# Transducer.net
KiCad netlist of a schematic drawn in Altium Designer
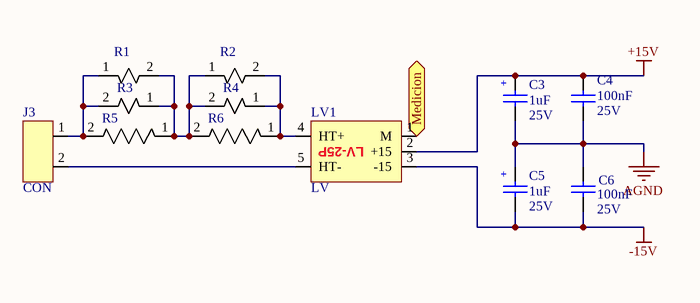
[diagram p0: Transducer.SchDoc]

(export (version "E")
  (design (tool "Eeschema 10.0.6"))
  (components
    (comp (ref "C3")
      (value "1uF")
      (footprint "CAP_1206 Tantalio")
      (description "Capacitor Tantalio")
      (fields (field (name "VOLTAGE") "25V"))
      (libsource (lib "Componentes_SOC") (part "Cap Tantalio 1206"))
    )
    (comp (ref "C4")
      (value "100nF")
      (footprint "CAP_0805")
      (description "Capacitor")
      (fields (field (name "VOLTAGE") "25V"))
      (libsource (lib "Componentes_SOC") (part "Cap_0805"))
    )
    (comp (ref "C5")
      (value "1uF")
      (footprint "CAP_1206 Tantalio")
      (description "Capacitor Tantalio")
      (fields (field (name "VOLTAGE") "25V"))
      (libsource (lib "Componentes_SOC") (part "Cap Tantalio 1206"))
    )
    (comp (ref "C6")
      (value "100nF")
      (footprint "CAP_0805")
      (description "Capacitor")
      (fields (field (name "VOLTAGE") "25V"))
      (libsource (lib "Componentes_SOC") (part "Cap_0805"))
    )
    (comp (ref "J3")
      (value "CON")
      (footprint "CON_282858-2")
      (description "282858-2")
      (libsource (lib "CON_282858-2") (part "CON_282858-2"))
    )
    (comp (ref "LV1")
      (value "LV")
      (footprint "LEM_LV 25-P")
      (description "LV 25-P")
      (libsource (lib "LEM_LV 25-P") (part "LEM_LV 25-P"))
    )
    (comp (ref "R1")
      (value "RES")
      (footprint "RES_MP925-15.0K-1%")
      (description "RES 50K OHM 25W 1% TO220")
      (libsource (lib "RES_MP925-15") (part "RES_MP925-15.0K-1%"))
    )
    (comp (ref "R2")
      (value "RES")
      (footprint "RES_MP925-15.0K-1%")
      (description "RES 50K OHM 25W 1% TO220")
      (libsource (lib "RES_MP925-15") (part "RES_MP925-15.0K-1%"))
    )
    (comp (ref "R3")
      (value "RES")
      (footprint "RES_MP925-15.0K-1%")
      (description "MP925-15.0K-1%")
      (libsource (lib "RES_MP925-15") (part "RES_MP925-15.0K-1%"))
    )
    (comp (ref "R4")
      (value "RES")
      (footprint "RES_MP925-15.0K-1%")
      (description "MP925-15.0K-1%")
      (libsource (lib "RES_MP925-15") (part "RES_MP925-15.0K-1%"))
    )
    (comp (ref "R5")
      (value "RES")
      (footprint "RES_RS00515K00FE73")
      (description "RS00515K00FE73")
      (libsource (lib "RES_RS00515K00FE73") (part "RES_RS00515K00FE73"))
    )
    (comp (ref "R6")
      (value "RES")
      (footprint "RES_RS00515K00FE73")
      (description "RS00515K00FE73")
      (libsource (lib "RES_RS00515K00FE73") (part "RES_RS00515K00FE73"))
    )
  )
  (nets
    (net (code "1") (name "+15V") (class "Default")
      (node (ref "C3") (pin "1") (pinfunction "1_1") (pintype "passive"))
      (node (ref "C4") (pin "1") (pinfunction "1_1") (pintype "passive"))
      (node (ref "LV1") (pin "2") (pinfunction "+15_2") (pintype "passive"))
    )
    (net (code "2") (name "-15V") (class "Default")
      (node (ref "C5") (pin "2") (pinfunction "2_2") (pintype "passive"))
      (node (ref "C6") (pin "2") (pinfunction "2_2") (pintype "passive"))
      (node (ref "LV1") (pin "3") (pinfunction "-15_3") (pintype "passive"))
    )
    (net (code "3") (name "/Medicion") (class "Default")
      (node (ref "LV1") (pin "1") (pinfunction "M_1") (pintype "passive"))
    )
    (net (code "4") (name "AGND") (class "Default")
      (node (ref "C3") (pin "2") (pinfunction "2_2") (pintype "passive"))
      (node (ref "C4") (pin "2") (pinfunction "2_2") (pintype "passive"))
      (node (ref "C5") (pin "1") (pinfunction "1_1") (pintype "passive"))
      (node (ref "C6") (pin "1") (pinfunction "1_1") (pintype "passive"))
    )
    (net (code "5") (name "Net-(LV1-HT+)") (class "Default")
      (node (ref "LV1") (pin "4") (pinfunction "HT+_4") (pintype "passive"))
      (node (ref "R2") (pin "2") (pinfunction "A_2") (pintype "passive"))
      (node (ref "R4") (pin "1") (pinfunction "C_1") (pintype "passive"))
      (node (ref "R6") (pin "1") (pinfunction "C_1") (pintype "passive"))
    )
    (net (code "6") (name "Net-(LV1-HT-)") (class "Default")
      (node (ref "J3") (pin "2") (pinfunction "2_2") (pintype "passive"))
      (node (ref "LV1") (pin "5") (pinfunction "HT-_5") (pintype "passive"))
    )
    (net (code "7") (name "Net-(R1-A)") (class "Default")
      (node (ref "R1") (pin "2") (pinfunction "A_2") (pintype "passive"))
      (node (ref "R2") (pin "1") (pinfunction "C_1") (pintype "passive"))
      (node (ref "R3") (pin "1") (pinfunction "C_1") (pintype "passive"))
      (node (ref "R4") (pin "2") (pinfunction "A_2") (pintype "passive"))
      (node (ref "R5") (pin "1") (pinfunction "C_1") (pintype "passive"))
      (node (ref "R6") (pin "2") (pinfunction "A_2") (pintype "passive"))
    )
    (net (code "8") (name "Net-(R1-C)") (class "Default")
      (node (ref "J3") (pin "1") (pinfunction "1_1") (pintype "passive"))
      (node (ref "R1") (pin "1") (pinfunction "C_1") (pintype "passive"))
      (node (ref "R3") (pin "2") (pinfunction "A_2") (pintype "passive"))
      (node (ref "R5") (pin "2") (pinfunction "A_2") (pintype "passive"))
    )
  )
)
